# FizziLagTester.net
KiCad netlist of a schematic drawn in EAGLE
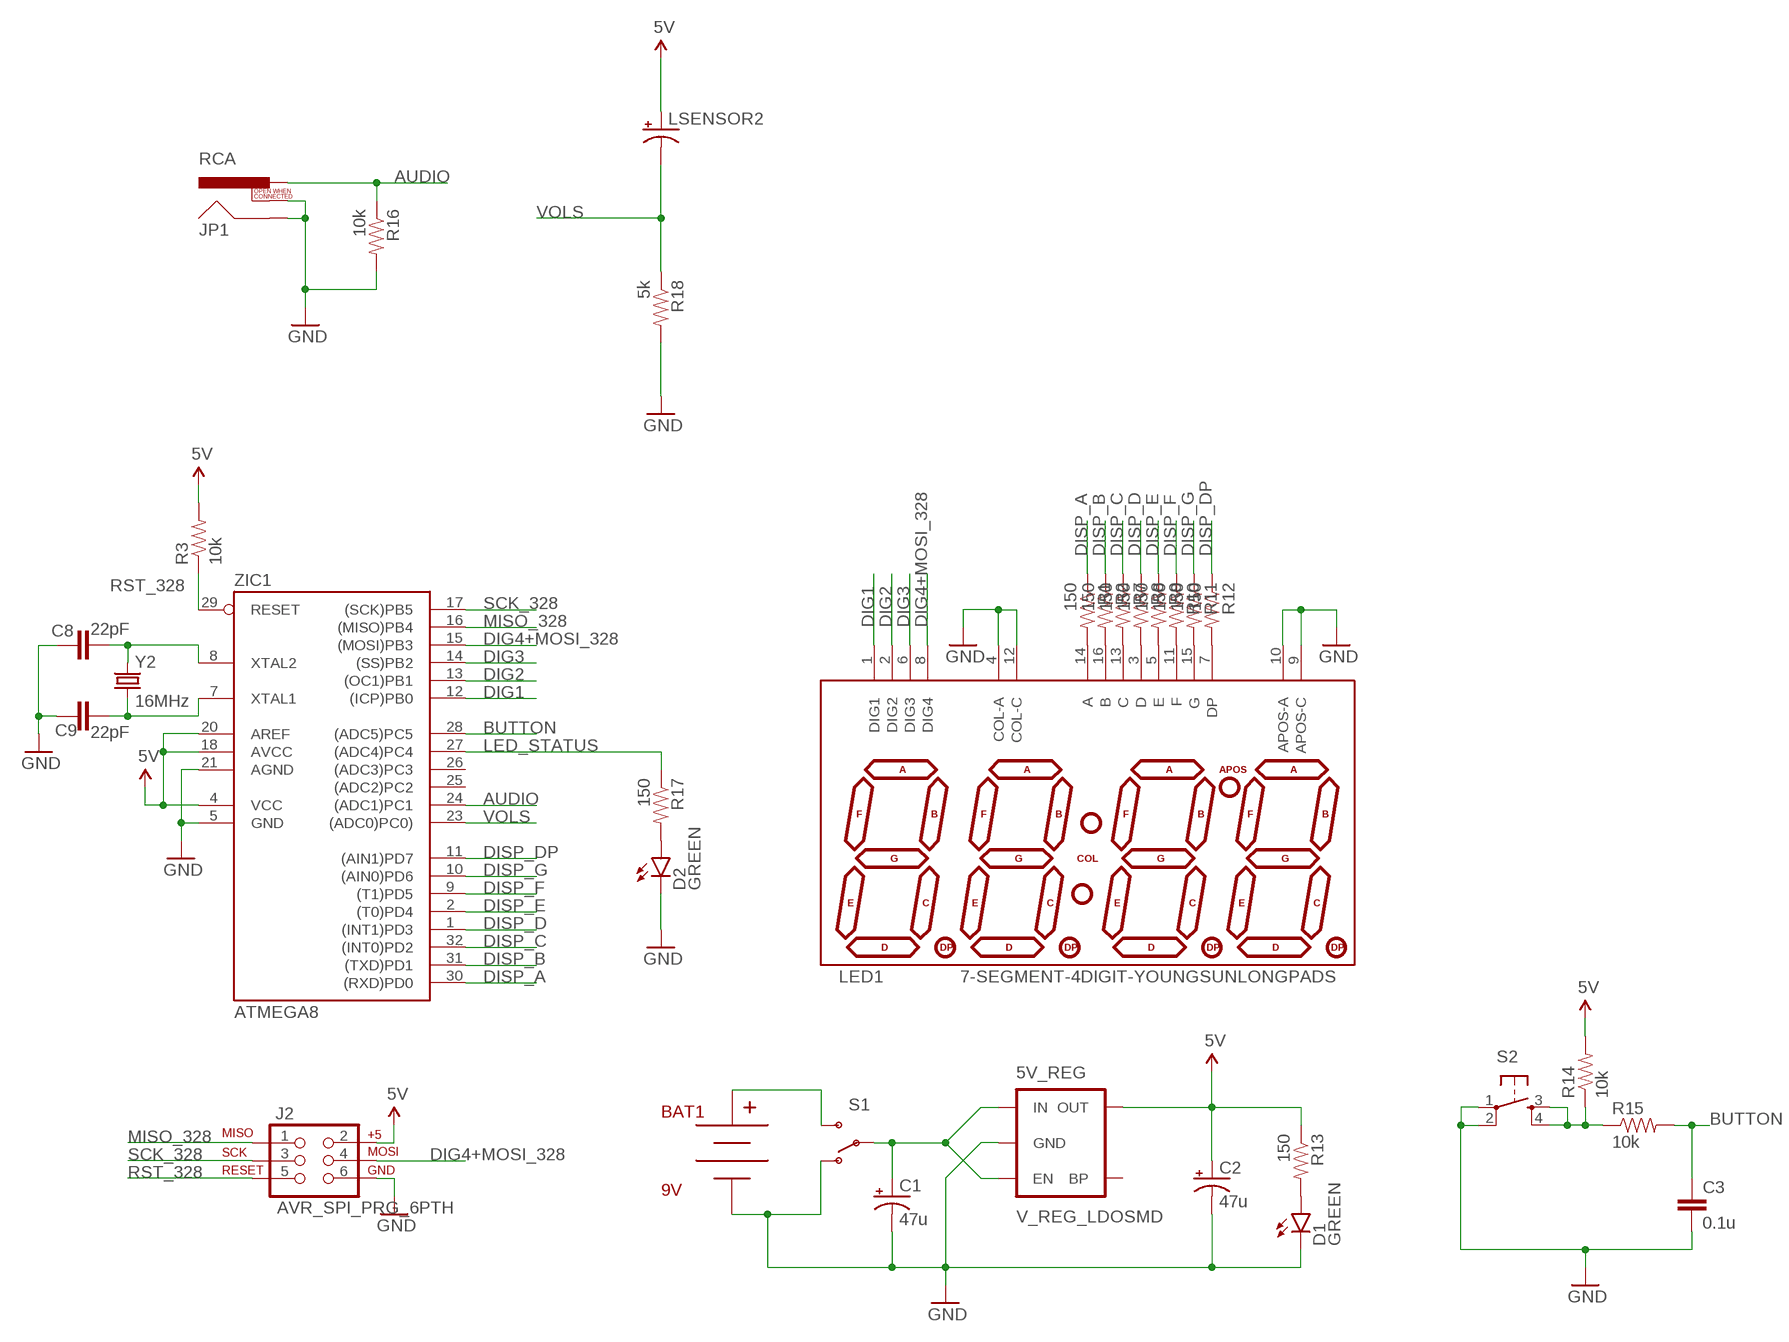
[diagram p0: schematic, sheet 1]

(export (version "E")
  (design (tool "Eeschema 10.0.6"))
  (components
    (comp (ref "5V_REG")
      (value "V_REG_LDOSMD")
      (footprint "eagle-import:SOT23-5")
      (libsource (lib "eagle-import") (part "V_REG_LDOSMD"))
    )
    (comp (ref "BAT1")
      (value "9V")
      (footprint "eagle-import:BC9VPC")
      (libsource (lib "eagle-import") (part "BC9VPC"))
    )
    (comp (ref "C1")
      (value "47u")
      (footprint "eagle-import:CPOL-RADIAL-100UF-25V")
      (libsource (lib "eagle-import") (part "CAP_POLPTH1"))
    )
    (comp (ref "C2")
      (value "47u")
      (footprint "eagle-import:CPOL-RADIAL-100UF-25V")
      (libsource (lib "eagle-import") (part "CAP_POLPTH1"))
    )
    (comp (ref "C3")
      (value "0.1u")
      (footprint "eagle-import:0603-CAP")
      (libsource (lib "eagle-import") (part "SparkFun-Capacitors_CAP0603-CAP"))
    )
    (comp (ref "C8")
      (value "22pF")
      (footprint "eagle-import:0603-CAP")
      (libsource (lib "eagle-import") (part "CAP0603-CAP"))
    )
    (comp (ref "C9")
      (value "22pF")
      (footprint "eagle-import:0603-CAP")
      (libsource (lib "eagle-import") (part "CAP0603-CAP"))
    )
    (comp (ref "D1")
      (value "GREEN")
      (footprint "eagle-import:LED-0603")
      (libsource (lib "eagle-import") (part "LED-GREEN0603"))
    )
    (comp (ref "D2")
      (value "GREEN")
      (footprint "eagle-import:LED-0603")
      (libsource (lib "eagle-import") (part "LED-GREEN0603"))
    )
    (comp (ref "J2")
      (value "AVR_SPI_PRG_6PTH")
      (footprint "eagle-import:2X3")
      (libsource (lib "eagle-import") (part "AVR_SPI_PRG_6PTH"))
    )
    (comp (ref "JP1")
      (value "RCA")
      (footprint "eagle-import:RCA")
      (libsource (lib "eagle-import") (part "RCA"))
    )
    (comp (ref "LED1")
      (value "7-SEGMENT-4DIGIT-YOUNGSUNLONGPADS")
      (footprint "eagle-import:7-SEGMENT-4DIGIT-YOUNGSUN-LONGPADS")
      (libsource (lib "eagle-import") (part "7-SEGMENT-4DIGIT-YOUNGSUNLONGPADS"))
    )
    (comp (ref "LSENSOR2")
      (value "CAP_POLPTH2")
      (footprint "eagle-import:CPOL-RADIAL-10UF-25V")
      (libsource (lib "eagle-import") (part "CAP_POLPTH2"))
    )
    (comp (ref "R1")
      (value "150")
      (footprint "eagle-import:0603-RES")
      (libsource (lib "eagle-import") (part "SparkFun-Passives_RESISTOR0603-RES"))
    )
    (comp (ref "R2")
      (value "150")
      (footprint "eagle-import:0603-RES")
      (libsource (lib "eagle-import") (part "SparkFun-Passives_RESISTOR0603-RES"))
    )
    (comp (ref "R3")
      (value "10k")
      (footprint "eagle-import:0603-RES")
      (libsource (lib "eagle-import") (part "RESISTOR0603-RES"))
    )
    (comp (ref "R7")
      (value "150")
      (footprint "eagle-import:0603-RES")
      (libsource (lib "eagle-import") (part "SparkFun-Passives_RESISTOR0603-RES"))
    )
    (comp (ref "R8")
      (value "150")
      (footprint "eagle-import:0603-RES")
      (libsource (lib "eagle-import") (part "SparkFun-Passives_RESISTOR0603-RES"))
    )
    (comp (ref "R9")
      (value "150")
      (footprint "eagle-import:0603-RES")
      (libsource (lib "eagle-import") (part "SparkFun-Passives_RESISTOR0603-RES"))
    )
    (comp (ref "R10")
      (value "150")
      (footprint "eagle-import:0603-RES")
      (libsource (lib "eagle-import") (part "SparkFun-Passives_RESISTOR0603-RES"))
    )
    (comp (ref "R11")
      (value "150")
      (footprint "eagle-import:0603-RES")
      (libsource (lib "eagle-import") (part "SparkFun-Passives_RESISTOR0603-RES"))
    )
    (comp (ref "R12")
      (value "150")
      (footprint "eagle-import:0603-RES")
      (libsource (lib "eagle-import") (part "SparkFun-Passives_RESISTOR0603-RES"))
    )
    (comp (ref "R13")
      (value "150")
      (footprint "eagle-import:0603-RES")
      (libsource (lib "eagle-import") (part "SparkFun-Passives_RESISTOR0603-RES"))
    )
    (comp (ref "R14")
      (value "10k")
      (footprint "eagle-import:0603-RES")
      (libsource (lib "eagle-import") (part "SparkFun-Passives_RESISTOR0603-RES"))
    )
    (comp (ref "R15")
      (value "10k")
      (footprint "eagle-import:0603-RES")
      (libsource (lib "eagle-import") (part "SparkFun-Passives_RESISTOR0603-RES"))
    )
    (comp (ref "R16")
      (value "10k")
      (footprint "eagle-import:0603-RES")
      (libsource (lib "eagle-import") (part "SparkFun-Passives_RESISTOR0603-RES"))
    )
    (comp (ref "R17")
      (value "150")
      (footprint "eagle-import:0603-RES")
      (libsource (lib "eagle-import") (part "SparkFun-Passives_RESISTOR0603-RES"))
    )
    (comp (ref "R18")
      (value "5k")
      (footprint "eagle-import:0603-RES")
      (libsource (lib "eagle-import") (part "SparkFun-Passives_RESISTOR0603-RES"))
    )
    (comp (ref "S1")
      (value "SWITCH-SPDTPTH")
      (footprint "eagle-import:SWITCH-SPDT")
      (libsource (lib "eagle-import") (part "SWITCH-SPDTPTH"))
    )
    (comp (ref "S2")
      (value "TAC_SWITCHPTH")
      (footprint "eagle-import:TACTILE-PTH")
      (libsource (lib "eagle-import") (part "TAC_SWITCHPTH"))
    )
    (comp (ref "Y2")
      (value "16MHz")
      (footprint "eagle-import:HC49US")
      (libsource (lib "eagle-import") (part "CRYSTALHC49US"))
    )
    (comp (ref "ZIC1")
      (value "ATMEGA8")
      (footprint "eagle-import:TQFP32-08")
      (libsource (lib "eagle-import") (part "AT90S4433A"))
    )
  )
  (nets
    (net (code "1") (name "/AUDIO") (class "Default")
      (node (ref "JP1") (pin "PIN") (pinfunction "PIN_PIN") (pintype "bidirectional"))
      (node (ref "R16") (pin "1") (pinfunction "1_1") (pintype "passive"))
      (node (ref "ZIC1") (pin "24") (pinfunction "(ADC1)PC1_24") (pintype "bidirectional"))
    )
    (net (code "2") (name "/BUTTON") (class "Default")
      (node (ref "C3") (pin "1") (pinfunction "1_1") (pintype "passive"))
      (node (ref "R15") (pin "2") (pinfunction "2_2") (pintype "passive"))
      (node (ref "ZIC1") (pin "28") (pinfunction "(ADC5)PC5_28") (pintype "bidirectional"))
    )
    (net (code "3") (name "/DIG1") (class "Default")
      (node (ref "LED1") (pin "1") (pinfunction "DIG1_1") (pintype "bidirectional"))
      (node (ref "ZIC1") (pin "12") (pinfunction "(ICP)PB0_12") (pintype "bidirectional"))
    )
    (net (code "4") (name "/DIG2") (class "Default")
      (node (ref "LED1") (pin "2") (pinfunction "DIG2_2") (pintype "bidirectional"))
      (node (ref "ZIC1") (pin "13") (pinfunction "(OC1)PB1_13") (pintype "bidirectional"))
    )
    (net (code "5") (name "/DIG3") (class "Default")
      (node (ref "LED1") (pin "6") (pinfunction "DIG3_6") (pintype "bidirectional"))
      (node (ref "ZIC1") (pin "14") (pinfunction "(SS)PB2_14") (pintype "bidirectional"))
    )
    (net (code "6") (name "/DIG4+MOSI_328") (class "Default")
      (node (ref "J2") (pin "4") (pinfunction "4_4") (pintype "passive"))
      (node (ref "LED1") (pin "8") (pinfunction "DIG4_8") (pintype "bidirectional"))
      (node (ref "ZIC1") (pin "15") (pinfunction "(MOSI)PB3_15") (pintype "bidirectional"))
    )
    (net (code "7") (name "/DISP_A") (class "Default")
      (node (ref "R1") (pin "1") (pinfunction "1_1") (pintype "passive"))
      (node (ref "ZIC1") (pin "30") (pinfunction "(RXD)PD0_30") (pintype "bidirectional"))
    )
    (net (code "8") (name "/DISP_B") (class "Default")
      (node (ref "R2") (pin "1") (pinfunction "1_1") (pintype "passive"))
      (node (ref "ZIC1") (pin "31") (pinfunction "(TXD)PD1_31") (pintype "bidirectional"))
    )
    (net (code "9") (name "/DISP_C") (class "Default")
      (node (ref "R7") (pin "1") (pinfunction "1_1") (pintype "passive"))
      (node (ref "ZIC1") (pin "32") (pinfunction "(INT0)PD2_32") (pintype "bidirectional"))
    )
    (net (code "10") (name "/DISP_D") (class "Default")
      (node (ref "R8") (pin "1") (pinfunction "1_1") (pintype "passive"))
      (node (ref "ZIC1") (pin "1") (pinfunction "(INT1)PD3_1") (pintype "bidirectional"))
    )
    (net (code "11") (name "/DISP_DP") (class "Default")
      (node (ref "R12") (pin "1") (pinfunction "1_1") (pintype "passive"))
      (node (ref "ZIC1") (pin "11") (pinfunction "(AIN1)PD7_11") (pintype "bidirectional"))
    )
    (net (code "12") (name "/DISP_E") (class "Default")
      (node (ref "R9") (pin "1") (pinfunction "1_1") (pintype "passive"))
      (node (ref "ZIC1") (pin "2") (pinfunction "(T0)PD4_2") (pintype "bidirectional"))
    )
    (net (code "13") (name "/DISP_F") (class "Default")
      (node (ref "R10") (pin "1") (pinfunction "1_1") (pintype "passive"))
      (node (ref "ZIC1") (pin "9") (pinfunction "(T1)PD5_9") (pintype "bidirectional"))
    )
    (net (code "14") (name "/DISP_G") (class "Default")
      (node (ref "R11") (pin "1") (pinfunction "1_1") (pintype "passive"))
      (node (ref "ZIC1") (pin "10") (pinfunction "(AIN0)PD6_10") (pintype "bidirectional"))
    )
    (net (code "15") (name "/LED_STATUS") (class "Default")
      (node (ref "R17") (pin "1") (pinfunction "1_1") (pintype "passive"))
      (node (ref "ZIC1") (pin "27") (pinfunction "(ADC4)PC4_27") (pintype "bidirectional"))
    )
    (net (code "16") (name "/MISO_328") (class "Default")
      (node (ref "J2") (pin "1") (pinfunction "1_1") (pintype "passive"))
      (node (ref "ZIC1") (pin "16") (pinfunction "(MISO)PB4_16") (pintype "bidirectional"))
    )
    (net (code "17") (name "/RST_328") (class "Default")
      (node (ref "J2") (pin "5") (pinfunction "5_5") (pintype "passive"))
      (node (ref "R3") (pin "1") (pinfunction "1_1") (pintype "passive"))
      (node (ref "ZIC1") (pin "29") (pinfunction "RESET_29") (pintype "input"))
    )
    (net (code "18") (name "/SCK_328") (class "Default")
      (node (ref "J2") (pin "3") (pinfunction "3_3") (pintype "passive"))
      (node (ref "ZIC1") (pin "17") (pinfunction "(SCK)PB5_17") (pintype "bidirectional"))
    )
    (net (code "19") (name "/VOLS") (class "Default")
      (node (ref "LSENSOR2") (pin "2") (pinfunction "-_2") (pintype "passive"))
      (node (ref "R18") (pin "1") (pinfunction "1_1") (pintype "passive"))
      (node (ref "ZIC1") (pin "23") (pinfunction "(ADC0)PC0)_23") (pintype "bidirectional"))
    )
    (net (code "20") (name "5V") (class "Default")
      (node (ref "5V_REG") (pin "5") (pinfunction "OUT_5") (pintype "passive"))
      (node (ref "C2") (pin "1") (pinfunction "+_1") (pintype "passive"))
      (node (ref "J2") (pin "2") (pinfunction "2_2") (pintype "passive"))
      (node (ref "LSENSOR2") (pin "1") (pinfunction "+_1") (pintype "passive"))
      (node (ref "R13") (pin "1") (pinfunction "1_1") (pintype "passive"))
      (node (ref "R14") (pin "2") (pinfunction "2_2") (pintype "passive"))
      (node (ref "R3") (pin "2") (pinfunction "2_2") (pintype "passive"))
      (node (ref "ZIC1") (pin "18") (pinfunction "AVCC_18") (pintype "power_in"))
      (node (ref "ZIC1") (pin "20") (pinfunction "AREF_20") (pintype "passive"))
      (node (ref "ZIC1") (pin "4") (pinfunction "VCC_4") (pintype "power_in"))
    )
    (net (code "21") (name "GND") (class "Default")
      (node (ref "5V_REG") (pin "2") (pinfunction "GND_2") (pintype "input"))
      (node (ref "BAT1") (pin "V-") (pinfunction "V-_V-") (pintype "bidirectional"))
      (node (ref "C1") (pin "2") (pinfunction "-_2") (pintype "passive"))
      (node (ref "C2") (pin "2") (pinfunction "-_2") (pintype "passive"))
      (node (ref "C3") (pin "2") (pinfunction "2_2") (pintype "passive"))
      (node (ref "C8") (pin "2") (pinfunction "2_2") (pintype "passive"))
      (node (ref "C9") (pin "2") (pinfunction "2_2") (pintype "passive"))
      (node (ref "D1") (pin "C") (pinfunction "C_C") (pintype "passive"))
      (node (ref "D2") (pin "C") (pinfunction "C_C") (pintype "passive"))
      (node (ref "J2") (pin "6") (pinfunction "6_6") (pintype "passive"))
      (node (ref "JP1") (pin "SHELL") (pinfunction "SHELL_SHELL") (pintype "bidirectional"))
      (node (ref "JP1") (pin "SWITCH") (pinfunction "SWITCH_SWITCH") (pintype "bidirectional"))
      (node (ref "LED1") (pin "10") (pinfunction "APOS-A_10") (pintype "bidirectional"))
      (node (ref "LED1") (pin "12") (pinfunction "COL-C_12") (pintype "bidirectional"))
      (node (ref "LED1") (pin "4") (pinfunction "COL-A_4") (pintype "bidirectional"))
      (node (ref "LED1") (pin "9") (pinfunction "APOS-C_9") (pintype "bidirectional"))
      (node (ref "R16") (pin "2") (pinfunction "2_2") (pintype "passive"))
      (node (ref "R18") (pin "2") (pinfunction "2_2") (pintype "passive"))
      (node (ref "S1") (pin "1") (pinfunction "O_1") (pintype "passive"))
      (node (ref "S2") (pin "1") (pinfunction "1_1") (pintype "passive"))
      (node (ref "S2") (pin "2") (pinfunction "2_2") (pintype "passive"))
      (node (ref "ZIC1") (pin "21") (pinfunction "AGND_21") (pintype "power_in"))
      (node (ref "ZIC1") (pin "5") (pinfunction "GND_5") (pintype "power_in"))
    )
    (net (code "22") (name "Net-(5V_REG-EN)") (class "Default")
      (node (ref "5V_REG") (pin "1") (pinfunction "IN_1") (pintype "input"))
      (node (ref "5V_REG") (pin "3") (pinfunction "EN_3") (pintype "input"))
      (node (ref "C1") (pin "1") (pinfunction "+_1") (pintype "passive"))
      (node (ref "S1") (pin "2") (pinfunction "P_2") (pintype "passive"))
    )
    (net (code "23") (name "Net-(D1-PadA)") (class "Default")
      (node (ref "D1") (pin "A") (pinfunction "A_A") (pintype "passive"))
      (node (ref "R13") (pin "2") (pinfunction "2_2") (pintype "passive"))
    )
    (net (code "24") (name "Net-(D2-PadA)") (class "Default")
      (node (ref "D2") (pin "A") (pinfunction "A_A") (pintype "passive"))
      (node (ref "R17") (pin "2") (pinfunction "2_2") (pintype "passive"))
    )
    (net (code "25") (name "Net-(LED1-A)") (class "Default")
      (node (ref "LED1") (pin "14") (pinfunction "A_14") (pintype "bidirectional"))
      (node (ref "R1") (pin "2") (pinfunction "2_2") (pintype "passive"))
    )
    (net (code "26") (name "Net-(LED1-B)") (class "Default")
      (node (ref "LED1") (pin "16") (pinfunction "B_16") (pintype "bidirectional"))
      (node (ref "R2") (pin "2") (pinfunction "2_2") (pintype "passive"))
    )
    (net (code "27") (name "Net-(LED1-C)") (class "Default")
      (node (ref "LED1") (pin "13") (pinfunction "C_13") (pintype "bidirectional"))
      (node (ref "R7") (pin "2") (pinfunction "2_2") (pintype "passive"))
    )
    (net (code "28") (name "Net-(LED1-D)") (class "Default")
      (node (ref "LED1") (pin "3") (pinfunction "D_3") (pintype "bidirectional"))
      (node (ref "R8") (pin "2") (pinfunction "2_2") (pintype "passive"))
    )
    (net (code "29") (name "Net-(LED1-DP)") (class "Default")
      (node (ref "LED1") (pin "7") (pinfunction "DP_7") (pintype "bidirectional"))
      (node (ref "R12") (pin "2") (pinfunction "2_2") (pintype "passive"))
    )
    (net (code "30") (name "Net-(LED1-E)") (class "Default")
      (node (ref "LED1") (pin "5") (pinfunction "E_5") (pintype "bidirectional"))
      (node (ref "R9") (pin "2") (pinfunction "2_2") (pintype "passive"))
    )
    (net (code "31") (name "Net-(LED1-F)") (class "Default")
      (node (ref "LED1") (pin "11") (pinfunction "F_11") (pintype "bidirectional"))
      (node (ref "R10") (pin "2") (pinfunction "2_2") (pintype "passive"))
    )
    (net (code "32") (name "Net-(LED1-G)") (class "Default")
      (node (ref "LED1") (pin "15") (pinfunction "G_15") (pintype "bidirectional"))
      (node (ref "R11") (pin "2") (pinfunction "2_2") (pintype "passive"))
    )
    (net (code "33") (name "Net-(R14-Pad1)") (class "Default")
      (node (ref "R14") (pin "1") (pinfunction "1_1") (pintype "passive"))
      (node (ref "R15") (pin "1") (pinfunction "1_1") (pintype "passive"))
      (node (ref "S2") (pin "3") (pinfunction "3_3") (pintype "passive"))
      (node (ref "S2") (pin "4") (pinfunction "4_4") (pintype "passive"))
    )
    (net (code "34") (name "Net-(S1-S)") (class "Default")
      (node (ref "BAT1") (pin "V+") (pinfunction "V+_V+") (pintype "bidirectional"))
      (node (ref "S1") (pin "3") (pinfunction "S_3") (pintype "passive"))
    )
    (net (code "35") (name "Net-(ZIC1-XTAL1)") (class "Default")
      (node (ref "C9") (pin "1") (pinfunction "1_1") (pintype "passive"))
      (node (ref "Y2") (pin "1") (pinfunction "1_1") (pintype "passive"))
      (node (ref "ZIC1") (pin "7") (pinfunction "XTAL1_7") (pintype "bidirectional"))
    )
    (net (code "36") (name "Net-(ZIC1-XTAL2)") (class "Default")
      (node (ref "C8") (pin "1") (pinfunction "1_1") (pintype "passive"))
      (node (ref "Y2") (pin "2") (pinfunction "2_2") (pintype "passive"))
      (node (ref "ZIC1") (pin "8") (pinfunction "XTAL2_8") (pintype "bidirectional"))
    )
    (net (code "37") (name "unconnected-(5V_REG-BP-Pad4)") (class "Default")
      (node (ref "5V_REG") (pin "4") (pinfunction "BP_4") (pintype "input"))
    )
    (net (code "38") (name "unconnected-(ZIC1-(ADC2)PC2-Pad25)") (class "Default")
      (node (ref "ZIC1") (pin "25") (pinfunction "(ADC2)PC2_25") (pintype "bidirectional"))
    )
    (net (code "39") (name "unconnected-(ZIC1-(ADC3)PC3-Pad26)") (class "Default")
      (node (ref "ZIC1") (pin "26") (pinfunction "(ADC3)PC3_26") (pintype "bidirectional"))
    )
  )
)
